# eagle_mini.net
KiCad netlist of a schematic drawn in EAGLE
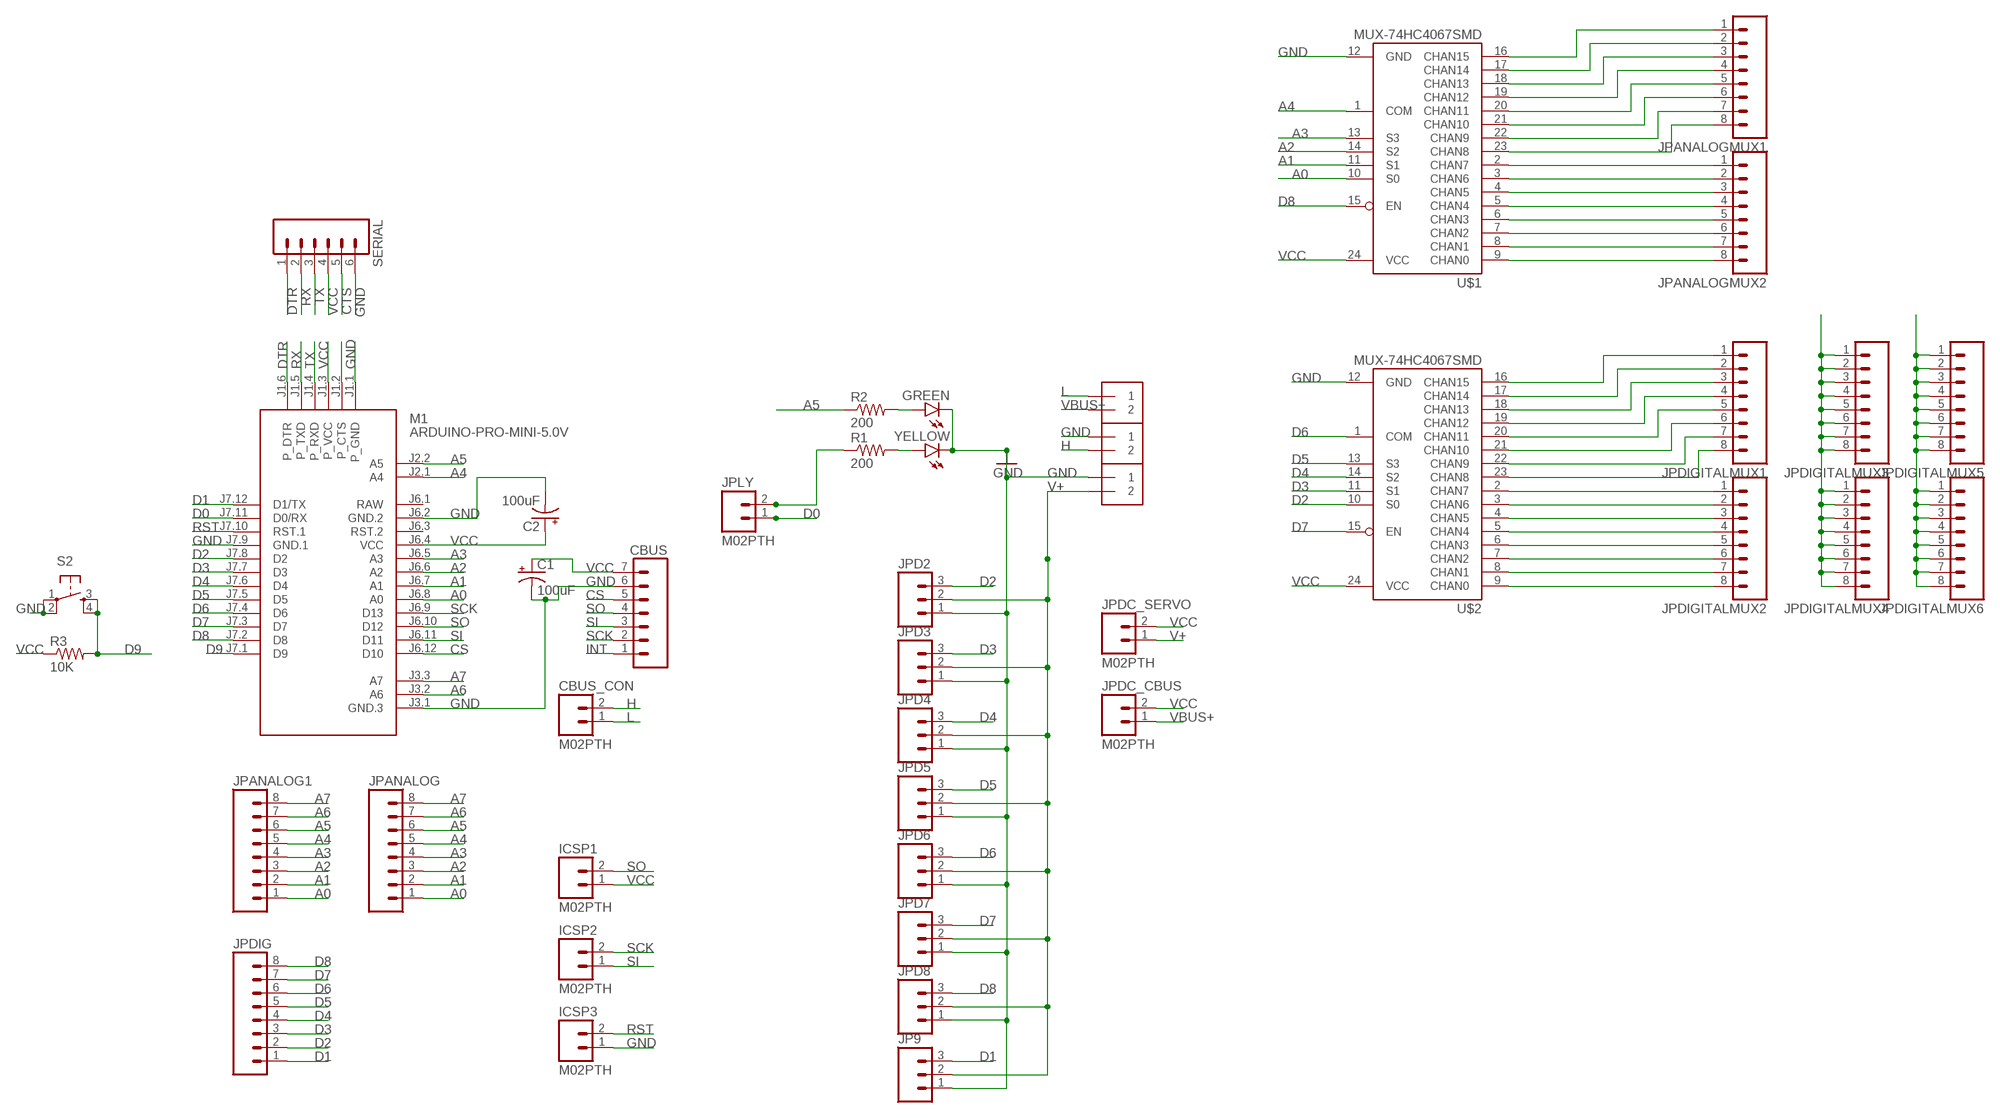
[diagram p0: schematic, sheet 1]

(export (version "E")
  (design (tool "Eeschema 10.0.6"))
  (components
    (comp (ref "C1")
      (value "100uF")
      (footprint "eagle-import:E2,5-6")
      (libsource (lib "eagle-import") (part "CPOL-USE2.5-6"))
    )
    (comp (ref "C2")
      (value "100uF")
      (footprint "eagle-import:E2,5-6")
      (libsource (lib "eagle-import") (part "CPOL-USE2.5-6"))
    )
    (comp (ref "CBUS")
      (value "M07")
      (footprint "eagle-import:1X07")
      (libsource (lib "eagle-import") (part "M07"))
    )
    (comp (ref "CBUS_CON")
      (value "M02PTH")
      (footprint "eagle-import:1X02")
      (libsource (lib "eagle-import") (part "M02PTH"))
    )
    (comp (ref "EXT_VCC")
      (value "1X2-3.5MM")
      (footprint "eagle-import:1X2-3.5MM")
      (libsource (lib "eagle-import") (part "1X2-3.5MM"))
    )
    (comp (ref "GREEN")
      (value "LED-3MM-NO_SILK")
      (footprint "eagle-import:LED3MM-NS")
      (libsource (lib "eagle-import") (part "LED-3MM-NO_SILK"))
    )
    (comp (ref "ICSP1")
      (value "M02PTH")
      (footprint "eagle-import:1X02")
      (libsource (lib "eagle-import") (part "M02PTH"))
    )
    (comp (ref "ICSP2")
      (value "M02PTH")
      (footprint "eagle-import:1X02")
      (libsource (lib "eagle-import") (part "M02PTH"))
    )
    (comp (ref "ICSP3")
      (value "M02PTH")
      (footprint "eagle-import:1X02")
      (libsource (lib "eagle-import") (part "M02PTH"))
    )
    (comp (ref "J1")
      (value "1X2-3.5MM")
      (footprint "eagle-import:1X2-3.5MM")
      (libsource (lib "eagle-import") (part "1X2-3.5MM"))
    )
    (comp (ref "J2")
      (value "1X2-3.5MM")
      (footprint "eagle-import:1X2-3.5MM")
      (libsource (lib "eagle-import") (part "1X2-3.5MM"))
    )
    (comp (ref "JP9")
      (value "M03PTH")
      (footprint "eagle-import:1X03")
      (libsource (lib "eagle-import") (part "M03PTH"))
    )
    (comp (ref "JPANALOG")
      (value "M08")
      (footprint "eagle-import:1X08_ROUND")
      (libsource (lib "eagle-import") (part "M08"))
    )
    (comp (ref "JPANALOG1")
      (value "M08")
      (footprint "eagle-import:1X08_ROUND")
      (libsource (lib "eagle-import") (part "M08"))
    )
    (comp (ref "JPANALOGMUX1")
      (value "M08")
      (footprint "eagle-import:1X08_ROUND")
      (libsource (lib "eagle-import") (part "M08"))
    )
    (comp (ref "JPANALOGMUX2")
      (value "M08")
      (footprint "eagle-import:1X08_ROUND")
      (libsource (lib "eagle-import") (part "M08"))
    )
    (comp (ref "JPD2")
      (value "M03PTH")
      (footprint "eagle-import:1X03")
      (libsource (lib "eagle-import") (part "M03PTH"))
    )
    (comp (ref "JPD3")
      (value "M03PTH")
      (footprint "eagle-import:1X03")
      (libsource (lib "eagle-import") (part "M03PTH"))
    )
    (comp (ref "JPD4")
      (value "M03PTH")
      (footprint "eagle-import:1X03")
      (libsource (lib "eagle-import") (part "M03PTH"))
    )
    (comp (ref "JPD5")
      (value "M03PTH")
      (footprint "eagle-import:1X03")
      (libsource (lib "eagle-import") (part "M03PTH"))
    )
    (comp (ref "JPD6")
      (value "M03PTH")
      (footprint "eagle-import:1X03")
      (libsource (lib "eagle-import") (part "M03PTH"))
    )
    (comp (ref "JPD7")
      (value "M03PTH")
      (footprint "eagle-import:1X03")
      (libsource (lib "eagle-import") (part "M03PTH"))
    )
    (comp (ref "JPD8")
      (value "M03PTH")
      (footprint "eagle-import:1X03")
      (libsource (lib "eagle-import") (part "M03PTH"))
    )
    (comp (ref "JPDC_CBUS")
      (value "M02PTH")
      (footprint "eagle-import:1X02")
      (libsource (lib "eagle-import") (part "M02PTH"))
    )
    (comp (ref "JPDC_SERVO")
      (value "M02PTH")
      (footprint "eagle-import:1X02")
      (libsource (lib "eagle-import") (part "M02PTH"))
    )
    (comp (ref "JPDIG")
      (value "M08")
      (footprint "eagle-import:1X08_ROUND")
      (libsource (lib "eagle-import") (part "M08"))
    )
    (comp (ref "JPDIGITALMUX1")
      (value "M08")
      (footprint "eagle-import:1X08_ROUND")
      (libsource (lib "eagle-import") (part "M08"))
    )
    (comp (ref "JPDIGITALMUX2")
      (value "M08")
      (footprint "eagle-import:1X08_ROUND")
      (libsource (lib "eagle-import") (part "M08"))
    )
    (comp (ref "JPDIGITALMUX3")
      (value "M08")
      (footprint "eagle-import:1X08_ROUND")
      (libsource (lib "eagle-import") (part "M08"))
    )
    (comp (ref "JPDIGITALMUX4")
      (value "M08")
      (footprint "eagle-import:1X08_ROUND")
      (libsource (lib "eagle-import") (part "M08"))
    )
    (comp (ref "JPDIGITALMUX5")
      (value "M08")
      (footprint "eagle-import:1X08_ROUND")
      (libsource (lib "eagle-import") (part "M08"))
    )
    (comp (ref "JPDIGITALMUX6")
      (value "M08")
      (footprint "eagle-import:1X08_ROUND")
      (libsource (lib "eagle-import") (part "M08"))
    )
    (comp (ref "JPLY")
      (value "M02PTH")
      (footprint "eagle-import:1X02")
      (libsource (lib "eagle-import") (part "M02PTH"))
    )
    (comp (ref "M1")
      (value "ARDUINO-PRO-MINI-5.0V")
      (footprint "eagle-import:ARDUINO-PRO-MINI")
      (libsource (lib "eagle-import") (part "ARDUINO-PRO-MINI-5.0V"))
    )
    (comp (ref "R1")
      (value "200")
      (footprint "eagle-import:AXIAL-0.3")
      (libsource (lib "eagle-import") (part "RESISTORAXIAL-0.3"))
    )
    (comp (ref "R2")
      (value "200")
      (footprint "eagle-import:AXIAL-0.3")
      (libsource (lib "eagle-import") (part "RESISTORAXIAL-0.3"))
    )
    (comp (ref "R3")
      (value "10K")
      (footprint "eagle-import:AXIAL-0.3")
      (libsource (lib "eagle-import") (part "RESISTORAXIAL-0.3"))
    )
    (comp (ref "S2")
      (value "TAC_SWITCHPTH")
      (footprint "eagle-import:TACTILE-PTH")
      (libsource (lib "eagle-import") (part "TAC_SWITCHPTH"))
    )
    (comp (ref "SERIAL")
      (value "M06SILK_FEMALE_PTH")
      (footprint "eagle-import:1X06")
      (libsource (lib "eagle-import") (part "M06SILK_FEMALE_PTH"))
    )
    (comp (ref "U$1")
      (value "MUX-74HC4067SMD")
      (footprint "eagle-import:SSOP24")
      (libsource (lib "eagle-import") (part "MUX-74HC4067SMD"))
    )
    (comp (ref "U$2")
      (value "MUX-74HC4067SMD")
      (footprint "eagle-import:SSOP24")
      (libsource (lib "eagle-import") (part "MUX-74HC4067SMD"))
    )
    (comp (ref "YELLOW")
      (value "LED-3MM-NO_SILK")
      (footprint "eagle-import:LED3MM-NS")
      (libsource (lib "eagle-import") (part "LED-3MM-NO_SILK"))
    )
  )
  (nets
    (net (code "1") (name "/A0") (class "Default")
      (node (ref "JPANALOG") (pin "1") (pinfunction "1_1") (pintype "passive"))
      (node (ref "JPANALOG1") (pin "1") (pinfunction "1_1") (pintype "passive"))
      (node (ref "M1") (pin "J6.8") (pinfunction "A0_J6.8") (pintype "bidirectional"))
      (node (ref "U$1") (pin "10") (pinfunction "S0_10") (pintype "input"))
    )
    (net (code "2") (name "/A1") (class "Default")
      (node (ref "JPANALOG") (pin "2") (pinfunction "2_2") (pintype "passive"))
      (node (ref "JPANALOG1") (pin "2") (pinfunction "2_2") (pintype "passive"))
      (node (ref "M1") (pin "J6.7") (pinfunction "A1_J6.7") (pintype "bidirectional"))
      (node (ref "U$1") (pin "11") (pinfunction "S1_11") (pintype "input"))
    )
    (net (code "3") (name "/A2") (class "Default")
      (node (ref "JPANALOG") (pin "3") (pinfunction "3_3") (pintype "passive"))
      (node (ref "JPANALOG1") (pin "3") (pinfunction "3_3") (pintype "passive"))
      (node (ref "M1") (pin "J6.6") (pinfunction "A2_J6.6") (pintype "bidirectional"))
      (node (ref "U$1") (pin "14") (pinfunction "S2_14") (pintype "input"))
    )
    (net (code "4") (name "/A3") (class "Default")
      (node (ref "JPANALOG") (pin "4") (pinfunction "4_4") (pintype "passive"))
      (node (ref "JPANALOG1") (pin "4") (pinfunction "4_4") (pintype "passive"))
      (node (ref "M1") (pin "J6.5") (pinfunction "A3_J6.5") (pintype "bidirectional"))
      (node (ref "U$1") (pin "13") (pinfunction "S3_13") (pintype "input"))
    )
    (net (code "5") (name "/A4") (class "Default")
      (node (ref "JPANALOG") (pin "5") (pinfunction "5_5") (pintype "passive"))
      (node (ref "JPANALOG1") (pin "5") (pinfunction "5_5") (pintype "passive"))
      (node (ref "M1") (pin "J2.1") (pinfunction "A4_J2.1") (pintype "bidirectional"))
      (node (ref "U$1") (pin "1") (pinfunction "COM_1") (pintype "bidirectional"))
    )
    (net (code "6") (name "/A5") (class "Default")
      (node (ref "JPANALOG") (pin "6") (pinfunction "6_6") (pintype "passive"))
      (node (ref "JPANALOG1") (pin "6") (pinfunction "6_6") (pintype "passive"))
      (node (ref "M1") (pin "J2.2") (pinfunction "A5_J2.2") (pintype "bidirectional"))
      (node (ref "R2") (pin "P$1") (pinfunction "1_P$1") (pintype "passive"))
    )
    (net (code "7") (name "/A6") (class "Default")
      (node (ref "JPANALOG") (pin "7") (pinfunction "7_7") (pintype "passive"))
      (node (ref "JPANALOG1") (pin "7") (pinfunction "7_7") (pintype "passive"))
      (node (ref "M1") (pin "J3.2") (pinfunction "A6_J3.2") (pintype "bidirectional"))
    )
    (net (code "8") (name "/A7") (class "Default")
      (node (ref "JPANALOG") (pin "8") (pinfunction "8_8") (pintype "passive"))
      (node (ref "JPANALOG1") (pin "8") (pinfunction "8_8") (pintype "passive"))
      (node (ref "M1") (pin "J3.3") (pinfunction "A7_J3.3") (pintype "bidirectional"))
    )
    (net (code "9") (name "/CS") (class "Default")
      (node (ref "CBUS") (pin "5") (pinfunction "5_5") (pintype "passive"))
      (node (ref "M1") (pin "J6.12") (pinfunction "D10_J6.12") (pintype "bidirectional"))
    )
    (net (code "10") (name "/CTS") (class "Default")
      (node (ref "SERIAL") (pin "5") (pinfunction "5_5") (pintype "passive"))
    )
    (net (code "11") (name "/D0") (class "Default")
      (node (ref "JPLY") (pin "1") (pinfunction "1_1") (pintype "passive"))
      (node (ref "M1") (pin "J7.11") (pinfunction "D0/RX_J7.11") (pintype "bidirectional"))
    )
    (net (code "12") (name "/D1") (class "Default")
      (node (ref "JP9") (pin "3") (pinfunction "3_3") (pintype "passive"))
      (node (ref "JPDIG") (pin "1") (pinfunction "1_1") (pintype "passive"))
      (node (ref "M1") (pin "J7.12") (pinfunction "D1/TX_J7.12") (pintype "bidirectional"))
    )
    (net (code "13") (name "/D2") (class "Default")
      (node (ref "JPD2") (pin "3") (pinfunction "3_3") (pintype "passive"))
      (node (ref "JPDIG") (pin "2") (pinfunction "2_2") (pintype "passive"))
      (node (ref "M1") (pin "J7.8") (pinfunction "D2_J7.8") (pintype "bidirectional"))
      (node (ref "U$2") (pin "10") (pinfunction "S0_10") (pintype "input"))
    )
    (net (code "14") (name "/D3") (class "Default")
      (node (ref "JPD3") (pin "3") (pinfunction "3_3") (pintype "passive"))
      (node (ref "JPDIG") (pin "3") (pinfunction "3_3") (pintype "passive"))
      (node (ref "M1") (pin "J7.7") (pinfunction "D3_J7.7") (pintype "bidirectional"))
      (node (ref "U$2") (pin "11") (pinfunction "S1_11") (pintype "input"))
    )
    (net (code "15") (name "/D4") (class "Default")
      (node (ref "JPD4") (pin "3") (pinfunction "3_3") (pintype "passive"))
      (node (ref "JPDIG") (pin "4") (pinfunction "4_4") (pintype "passive"))
      (node (ref "M1") (pin "J7.6") (pinfunction "D4_J7.6") (pintype "bidirectional"))
      (node (ref "U$2") (pin "14") (pinfunction "S2_14") (pintype "input"))
    )
    (net (code "16") (name "/D5") (class "Default")
      (node (ref "JPD5") (pin "3") (pinfunction "3_3") (pintype "passive"))
      (node (ref "JPDIG") (pin "5") (pinfunction "5_5") (pintype "passive"))
      (node (ref "M1") (pin "J7.5") (pinfunction "D5_J7.5") (pintype "bidirectional"))
      (node (ref "U$2") (pin "13") (pinfunction "S3_13") (pintype "input"))
    )
    (net (code "17") (name "/D6") (class "Default")
      (node (ref "JPD6") (pin "3") (pinfunction "3_3") (pintype "passive"))
      (node (ref "JPDIG") (pin "6") (pinfunction "6_6") (pintype "passive"))
      (node (ref "M1") (pin "J7.4") (pinfunction "D6_J7.4") (pintype "bidirectional"))
      (node (ref "U$2") (pin "1") (pinfunction "COM_1") (pintype "bidirectional"))
    )
    (net (code "18") (name "/D7") (class "Default")
      (node (ref "JPD7") (pin "3") (pinfunction "3_3") (pintype "passive"))
      (node (ref "JPDIG") (pin "7") (pinfunction "7_7") (pintype "passive"))
      (node (ref "M1") (pin "J7.3") (pinfunction "D7_J7.3") (pintype "bidirectional"))
      (node (ref "U$2") (pin "15") (pinfunction "EN_15") (pintype "input"))
    )
    (net (code "19") (name "/D8") (class "Default")
      (node (ref "JPD8") (pin "3") (pinfunction "3_3") (pintype "passive"))
      (node (ref "JPDIG") (pin "8") (pinfunction "8_8") (pintype "passive"))
      (node (ref "M1") (pin "J7.2") (pinfunction "D8_J7.2") (pintype "bidirectional"))
      (node (ref "U$1") (pin "15") (pinfunction "EN_15") (pintype "input"))
    )
    (net (code "20") (name "/D9") (class "Default")
      (node (ref "M1") (pin "J7.1") (pinfunction "D9_J7.1") (pintype "bidirectional"))
      (node (ref "R3") (pin "P$2") (pinfunction "2_P$2") (pintype "passive"))
      (node (ref "S2") (pin "3") (pinfunction "3_3") (pintype "passive"))
      (node (ref "S2") (pin "4") (pinfunction "4_4") (pintype "passive"))
    )
    (net (code "21") (name "/DTR") (class "Default")
      (node (ref "M1") (pin "J1.6") (pinfunction "P_DTR_J1.6") (pintype "bidirectional"))
      (node (ref "SERIAL") (pin "1") (pinfunction "1_1") (pintype "passive"))
    )
    (net (code "22") (name "/H") (class "Default")
      (node (ref "CBUS_CON") (pin "2") (pinfunction "2_2") (pintype "passive"))
      (node (ref "J1") (pin "2") (pinfunction "2_2") (pintype "passive"))
    )
    (net (code "23") (name "/INT") (class "Default")
      (node (ref "CBUS") (pin "1") (pinfunction "1_1") (pintype "passive"))
    )
    (net (code "24") (name "/L") (class "Default")
      (node (ref "CBUS_CON") (pin "1") (pinfunction "1_1") (pintype "passive"))
      (node (ref "J2") (pin "1") (pinfunction "1_1") (pintype "passive"))
    )
    (net (code "25") (name "/RAW") (class "Default")
      (node (ref "M1") (pin "J6.1") (pinfunction "RAW_J6.1") (pintype "power_in"))
    )
    (net (code "26") (name "/RST") (class "Default")
      (node (ref "ICSP3") (pin "2") (pinfunction "2_2") (pintype "passive"))
      (node (ref "M1") (pin "J7.10") (pinfunction "RST.1_J7.10") (pintype "bidirectional"))
    )
    (net (code "27") (name "/RX") (class "Default")
      (node (ref "M1") (pin "J1.5") (pinfunction "P_TXD_J1.5") (pintype "bidirectional"))
      (node (ref "SERIAL") (pin "2") (pinfunction "2_2") (pintype "passive"))
    )
    (net (code "28") (name "/SCK") (class "Default")
      (node (ref "CBUS") (pin "2") (pinfunction "2_2") (pintype "passive"))
      (node (ref "ICSP2") (pin "2") (pinfunction "2_2") (pintype "passive"))
      (node (ref "M1") (pin "J6.9") (pinfunction "D13_J6.9") (pintype "bidirectional"))
    )
    (net (code "29") (name "/SI") (class "Default")
      (node (ref "CBUS") (pin "3") (pinfunction "3_3") (pintype "passive"))
      (node (ref "ICSP2") (pin "1") (pinfunction "1_1") (pintype "passive"))
      (node (ref "M1") (pin "J6.11") (pinfunction "D11_J6.11") (pintype "bidirectional"))
    )
    (net (code "30") (name "/SO") (class "Default")
      (node (ref "CBUS") (pin "4") (pinfunction "4_4") (pintype "passive"))
      (node (ref "ICSP1") (pin "2") (pinfunction "2_2") (pintype "passive"))
      (node (ref "M1") (pin "J6.10") (pinfunction "D12_J6.10") (pintype "bidirectional"))
    )
    (net (code "31") (name "/TX") (class "Default")
      (node (ref "M1") (pin "J1.4") (pinfunction "P_RXD_J1.4") (pintype "bidirectional"))
      (node (ref "SERIAL") (pin "3") (pinfunction "3_3") (pintype "passive"))
    )
    (net (code "32") (name "/V+") (class "Default")
      (node (ref "EXT_VCC") (pin "2") (pinfunction "2_2") (pintype "passive"))
      (node (ref "JP9") (pin "2") (pinfunction "2_2") (pintype "passive"))
      (node (ref "JPD2") (pin "2") (pinfunction "2_2") (pintype "passive"))
      (node (ref "JPD3") (pin "2") (pinfunction "2_2") (pintype "passive"))
      (node (ref "JPD4") (pin "2") (pinfunction "2_2") (pintype "passive"))
      (node (ref "JPD5") (pin "2") (pinfunction "2_2") (pintype "passive"))
      (node (ref "JPD6") (pin "2") (pinfunction "2_2") (pintype "passive"))
      (node (ref "JPD7") (pin "2") (pinfunction "2_2") (pintype "passive"))
      (node (ref "JPD8") (pin "2") (pinfunction "2_2") (pintype "passive"))
      (node (ref "JPDC_SERVO") (pin "1") (pinfunction "1_1") (pintype "passive"))
      (node (ref "JPDIGITALMUX5") (pin "1") (pinfunction "1_1") (pintype "passive"))
      (node (ref "JPDIGITALMUX5") (pin "2") (pinfunction "2_2") (pintype "passive"))
      (node (ref "JPDIGITALMUX5") (pin "3") (pinfunction "3_3") (pintype "passive"))
      (node (ref "JPDIGITALMUX5") (pin "4") (pinfunction "4_4") (pintype "passive"))
      (node (ref "JPDIGITALMUX5") (pin "5") (pinfunction "5_5") (pintype "passive"))
      (node (ref "JPDIGITALMUX5") (pin "6") (pinfunction "6_6") (pintype "passive"))
      (node (ref "JPDIGITALMUX5") (pin "7") (pinfunction "7_7") (pintype "passive"))
      (node (ref "JPDIGITALMUX5") (pin "8") (pinfunction "8_8") (pintype "passive"))
      (node (ref "JPDIGITALMUX6") (pin "1") (pinfunction "1_1") (pintype "passive"))
      (node (ref "JPDIGITALMUX6") (pin "2") (pinfunction "2_2") (pintype "passive"))
      (node (ref "JPDIGITALMUX6") (pin "3") (pinfunction "3_3") (pintype "passive"))
      (node (ref "JPDIGITALMUX6") (pin "4") (pinfunction "4_4") (pintype "passive"))
      (node (ref "JPDIGITALMUX6") (pin "5") (pinfunction "5_5") (pintype "passive"))
      (node (ref "JPDIGITALMUX6") (pin "6") (pinfunction "6_6") (pintype "passive"))
      (node (ref "JPDIGITALMUX6") (pin "7") (pinfunction "7_7") (pintype "passive"))
      (node (ref "JPDIGITALMUX6") (pin "8") (pinfunction "8_8") (pintype "passive"))
    )
    (net (code "33") (name "/VBUS+") (class "Default")
      (node (ref "J2") (pin "2") (pinfunction "2_2") (pintype "passive"))
      (node (ref "JPDC_CBUS") (pin "1") (pinfunction "1_1") (pintype "passive"))
    )
    (net (code "34") (name "/VCC") (class "Default")
      (node (ref "C1") (pin "+") (pinfunction "+_+") (pintype "passive"))
      (node (ref "C2") (pin "+") (pinfunction "+_+") (pintype "passive"))
      (node (ref "CBUS") (pin "7") (pinfunction "7_7") (pintype "passive"))
      (node (ref "ICSP1") (pin "1") (pinfunction "1_1") (pintype "passive"))
      (node (ref "JPDC_CBUS") (pin "2") (pinfunction "2_2") (pintype "passive"))
      (node (ref "JPDC_SERVO") (pin "2") (pinfunction "2_2") (pintype "passive"))
      (node (ref "M1") (pin "J1.3") (pinfunction "P_VCC_J1.3") (pintype "bidirectional"))
      (node (ref "M1") (pin "J6.4") (pinfunction "VCC_J6.4") (pintype "power_in"))
      (node (ref "R3") (pin "P$1") (pinfunction "1_P$1") (pintype "passive"))
      (node (ref "SERIAL") (pin "4") (pinfunction "4_4") (pintype "passive"))
      (node (ref "U$1") (pin "24") (pinfunction "VCC_24") (pintype "bidirectional"))
      (node (ref "U$2") (pin "24") (pinfunction "VCC_24") (pintype "bidirectional"))
    )
    (net (code "35") (name "GND") (class "Default")
      (node (ref "C1") (pin "-") (pinfunction "-_-") (pintype "passive"))
      (node (ref "C2") (pin "-") (pinfunction "-_-") (pintype "passive"))
      (node (ref "CBUS") (pin "6") (pinfunction "6_6") (pintype "passive"))
      (node (ref "EXT_VCC") (pin "1") (pinfunction "1_1") (pintype "passive"))
      (node (ref "GREEN") (pin "K") (pinfunction "C_K") (pintype "passive"))
      (node (ref "ICSP3") (pin "1") (pinfunction "1_1") (pintype "passive"))
      (node (ref "J1") (pin "1") (pinfunction "1_1") (pintype "passive"))
      (node (ref "JP9") (pin "1") (pinfunction "1_1") (pintype "passive"))
      (node (ref "JPD2") (pin "1") (pinfunction "1_1") (pintype "passive"))
      (node (ref "JPD3") (pin "1") (pinfunction "1_1") (pintype "passive"))
      (node (ref "JPD4") (pin "1") (pinfunction "1_1") (pintype "passive"))
      (node (ref "JPD5") (pin "1") (pinfunction "1_1") (pintype "passive"))
      (node (ref "JPD6") (pin "1") (pinfunction "1_1") (pintype "passive"))
      (node (ref "JPD7") (pin "1") (pinfunction "1_1") (pintype "passive"))
      (node (ref "JPD8") (pin "1") (pinfunction "1_1") (pintype "passive"))
      (node (ref "JPDIGITALMUX3") (pin "1") (pinfunction "1_1") (pintype "passive"))
      (node (ref "JPDIGITALMUX3") (pin "2") (pinfunction "2_2") (pintype "passive"))
      (node (ref "JPDIGITALMUX3") (pin "3") (pinfunction "3_3") (pintype "passive"))
      (node (ref "JPDIGITALMUX3") (pin "4") (pinfunction "4_4") (pintype "passive"))
      (node (ref "JPDIGITALMUX3") (pin "5") (pinfunction "5_5") (pintype "passive"))
      (node (ref "JPDIGITALMUX3") (pin "6") (pinfunction "6_6") (pintype "passive"))
      (node (ref "JPDIGITALMUX3") (pin "7") (pinfunction "7_7") (pintype "passive"))
      (node (ref "JPDIGITALMUX3") (pin "8") (pinfunction "8_8") (pintype "passive"))
      (node (ref "JPDIGITALMUX4") (pin "1") (pinfunction "1_1") (pintype "passive"))
      (node (ref "JPDIGITALMUX4") (pin "2") (pinfunction "2_2") (pintype "passive"))
      (node (ref "JPDIGITALMUX4") (pin "3") (pinfunction "3_3") (pintype "passive"))
      (node (ref "JPDIGITALMUX4") (pin "4") (pinfunction "4_4") (pintype "passive"))
      (node (ref "JPDIGITALMUX4") (pin "5") (pinfunction "5_5") (pintype "passive"))
      (node (ref "JPDIGITALMUX4") (pin "6") (pinfunction "6_6") (pintype "passive"))
      (node (ref "JPDIGITALMUX4") (pin "7") (pinfunction "7_7") (pintype "passive"))
      (node (ref "JPDIGITALMUX4") (pin "8") (pinfunction "8_8") (pintype "passive"))
      (node (ref "M1") (pin "J1.1") (pinfunction "P_GND_J1.1") (pintype "bidirectional"))
      (node (ref "M1") (pin "J3.1") (pinfunction "GND.3_J3.1") (pintype "bidirectional"))
      (node (ref "M1") (pin "J6.2") (pinfunction "GND.2_J6.2") (pintype "power_in"))
      (node (ref "M1") (pin "J7.9") (pinfunction "GND.1_J7.9") (pintype "power_in"))
      (node (ref "S2") (pin "1") (pinfunction "1_1") (pintype "passive"))
      (node (ref "S2") (pin "2") (pinfunction "2_2") (pintype "passive"))
      (node (ref "SERIAL") (pin "6") (pinfunction "6_6") (pintype "passive"))
      (node (ref "U$1") (pin "12") (pinfunction "GND_12") (pintype "bidirectional"))
      (node (ref "U$2") (pin "12") (pinfunction "GND_12") (pintype "bidirectional"))
      (node (ref "YELLOW") (pin "K") (pinfunction "C_K") (pintype "passive"))
    )
    (net (code "36") (name "Net-(R1-1)") (class "Default")
      (node (ref "JPLY") (pin "2") (pinfunction "2_2") (pintype "passive"))
      (node (ref "R1") (pin "P$1") (pinfunction "1_P$1") (pintype "passive"))
    )
    (net (code "37") (name "Net-(R1-2)") (class "Default")
      (node (ref "R1") (pin "P$2") (pinfunction "2_P$2") (pintype "passive"))
      (node (ref "YELLOW") (pin "A") (pinfunction "A_A") (pintype "passive"))
    )
    (net (code "38") (name "Net-(R2-2)") (class "Default")
      (node (ref "GREEN") (pin "A") (pinfunction "A_A") (pintype "passive"))
      (node (ref "R2") (pin "P$2") (pinfunction "2_P$2") (pintype "passive"))
    )
    (net (code "39") (name "Net-(U$1-CHAN0)") (class "Default")
      (node (ref "JPANALOGMUX2") (pin "8") (pinfunction "8_8") (pintype "passive"))
      (node (ref "U$1") (pin "9") (pinfunction "CHAN0_9") (pintype "bidirectional"))
    )
    (net (code "40") (name "Net-(U$1-CHAN1)") (class "Default")
      (node (ref "JPANALOGMUX2") (pin "7") (pinfunction "7_7") (pintype "passive"))
      (node (ref "U$1") (pin "8") (pinfunction "CHAN1_8") (pintype "bidirectional"))
    )
    (net (code "41") (name "Net-(U$1-CHAN2)") (class "Default")
      (node (ref "JPANALOGMUX2") (pin "6") (pinfunction "6_6") (pintype "passive"))
      (node (ref "U$1") (pin "7") (pinfunction "CHAN2_7") (pintype "bidirectional"))
    )
    (net (code "42") (name "Net-(U$1-CHAN3)") (class "Default")
      (node (ref "JPANALOGMUX2") (pin "5") (pinfunction "5_5") (pintype "passive"))
      (node (ref "U$1") (pin "6") (pinfunction "CHAN3_6") (pintype "bidirectional"))
    )
    (net (code "43") (name "Net-(U$1-CHAN4)") (class "Default")
      (node (ref "JPANALOGMUX2") (pin "4") (pinfunction "4_4") (pintype "passive"))
      (node (ref "U$1") (pin "5") (pinfunction "CHAN4_5") (pintype "bidirectional"))
    )
    (net (code "44") (name "Net-(U$1-CHAN5)") (class "Default")
      (node (ref "JPANALOGMUX2") (pin "3") (pinfunction "3_3") (pintype "passive"))
      (node (ref "U$1") (pin "4") (pinfunction "CHAN5_4") (pintype "bidirectional"))
    )
    (net (code "45") (name "Net-(U$1-CHAN6)") (class "Default")
      (node (ref "JPANALOGMUX2") (pin "2") (pinfunction "2_2") (pintype "passive"))
      (node (ref "U$1") (pin "3") (pinfunction "CHAN6_3") (pintype "bidirectional"))
    )
    (net (code "46") (name "Net-(U$1-CHAN7)") (class "Default")
      (node (ref "JPANALOGMUX2") (pin "1") (pinfunction "1_1") (pintype "passive"))
      (node (ref "U$1") (pin "2") (pinfunction "CHAN7_2") (pintype "bidirectional"))
    )
    (net (code "47") (name "Net-(U$1-CHAN8)") (class "Default")
      (node (ref "JPANALOGMUX1") (pin "8") (pinfunction "8_8") (pintype "passive"))
      (node (ref "U$1") (pin "23") (pinfunction "CHAN8_23") (pintype "bidirectional"))
    )
    (net (code "48") (name "Net-(U$1-CHAN9)") (class "Default")
      (node (ref "JPANALOGMUX1") (pin "7") (pinfunction "7_7") (pintype "passive"))
      (node (ref "U$1") (pin "22") (pinfunction "CHAN9_22") (pintype "bidirectional"))
    )
    (net (code "49") (name "Net-(U$1-CHAN10)") (class "Default")
      (node (ref "JPANALOGMUX1") (pin "6") (pinfunction "6_6") (pintype "passive"))
      (node (ref "U$1") (pin "21") (pinfunction "CHAN10_21") (pintype "bidirectional"))
    )
    (net (code "50") (name "Net-(U$1-CHAN11)") (class "Default")
      (node (ref "JPANALOGMUX1") (pin "5") (pinfunction "5_5") (pintype "passive"))
      (node (ref "U$1") (pin "20") (pinfunction "CHAN11_20") (pintype "bidirectional"))
    )
    (net (code "51") (name "Net-(U$1-CHAN12)") (class "Default")
      (node (ref "JPANALOGMUX1") (pin "4") (pinfunction "4_4") (pintype "passive"))
      (node (ref "U$1") (pin "19") (pinfunction "CHAN12_19") (pintype "bidirectional"))
    )
    (net (code "52") (name "Net-(U$1-CHAN13)") (class "Default")
      (node (ref "JPANALOGMUX1") (pin "3") (pinfunction "3_3") (pintype "passive"))
      (node (ref "U$1") (pin "18") (pinfunction "CHAN13_18") (pintype "bidirectional"))
    )
    (net (code "53") (name "Net-(U$1-CHAN14)") (class "Default")
      (node (ref "JPANALOGMUX1") (pin "2") (pinfunction "2_2") (pintype "passive"))
      (node (ref "U$1") (pin "17") (pinfunction "CHAN14_17") (pintype "bidirectional"))
    )
    (net (code "54") (name "Net-(U$1-CHAN15)") (class "Default")
      (node (ref "JPANALOGMUX1") (pin "1") (pinfunction "1_1") (pintype "passive"))
      (node (ref "U$1") (pin "16") (pinfunction "CHAN15_16") (pintype "bidirectional"))
    )
    (net (code "55") (name "Net-(U$2-CHAN0)") (class "Default")
      (node (ref "JPDIGITALMUX2") (pin "8") (pinfunction "8_8") (pintype "passive"))
      (node (ref "U$2") (pin "9") (pinfunction "CHAN0_9") (pintype "bidirectional"))
    )
    (net (code "56") (name "Net-(U$2-CHAN1)") (class "Default")
      (node (ref "JPDIGITALMUX2") (pin "7") (pinfunction "7_7") (pintype "passive"))
      (node (ref "U$2") (pin "8") (pinfunction "CHAN1_8") (pintype "bidirectional"))
    )
    (net (code "57") (name "Net-(U$2-CHAN2)") (class "Default")
      (node (ref "JPDIGITALMUX2") (pin "6") (pinfunction "6_6") (pintype "passive"))
      (node (ref "U$2") (pin "7") (pinfunction "CHAN2_7") (pintype "bidirectional"))
    )
    (net (code "58") (name "Net-(U$2-CHAN3)") (class "Default")
      (node (ref "JPDIGITALMUX2") (pin "5") (pinfunction "5_5") (pintype "passive"))
      (node (ref "U$2") (pin "6") (pinfunction "CHAN3_6") (pintype "bidirectional"))
    )
    (net (code "59") (name "Net-(U$2-CHAN4)") (class "Default")
      (node (ref "JPDIGITALMUX2") (pin "4") (pinfunction "4_4") (pintype "passive"))
      (node (ref "U$2") (pin "5") (pinfunction "CHAN4_5") (pintype "bidirectional"))
    )
    (net (code "60") (name "Net-(U$2-CHAN5)") (class "Default")
      (node (ref "JPDIGITALMUX2") (pin "3") (pinfunction "3_3") (pintype "passive"))
      (node (ref "U$2") (pin "4") (pinfunction "CHAN5_4") (pintype "bidirectional"))
    )
    (net (code "61") (name "Net-(U$2-CHAN6)") (class "Default")
      (node (ref "JPDIGITALMUX2") (pin "2") (pinfunction "2_2") (pintype "passive"))
      (node (ref "U$2") (pin "3") (pinfunction "CHAN6_3") (pintype "bidirectional"))
    )
    (net (code "62") (name "Net-(U$2-CHAN7)") (class "Default")
      (node (ref "JPDIGITALMUX2") (pin "1") (pinfunction "1_1") (pintype "passive"))
      (node (ref "U$2") (pin "2") (pinfunction "CHAN7_2") (pintype "bidirectional"))
    )
    (net (code "63") (name "Net-(U$2-CHAN8)") (class "Default")
      (node (ref "JPDIGITALMUX1") (pin "8") (pinfunction "8_8") (pintype "passive"))
      (node (ref "U$2") (pin "23") (pinfunction "CHAN8_23") (pintype "bidirectional"))
    )
    (net (code "64") (name "Net-(U$2-CHAN9)") (class "Default")
      (node (ref "JPDIGITALMUX1") (pin "7") (pinfunction "7_7") (pintype "passive"))
      (node (ref "U$2") (pin "22") (pinfunction "CHAN9_22") (pintype "bidirectional"))
    )
    (net (code "65") (name "Net-(U$2-CHAN10)") (class "Default")
      (node (ref "JPDIGITALMUX1") (pin "6") (pinfunction "6_6") (pintype "passive"))
      (node (ref "U$2") (pin "21") (pinfunction "CHAN10_21") (pintype "bidirectional"))
    )
    (net (code "66") (name "Net-(U$2-CHAN11)") (class "Default")
      (node (ref "JPDIGITALMUX1") (pin "5") (pinfunction "5_5") (pintype "passive"))
      (node (ref "U$2") (pin "20") (pinfunction "CHAN11_20") (pintype "bidirectional"))
    )
    (net (code "67") (name "Net-(U$2-CHAN12)") (class "Default")
      (node (ref "JPDIGITALMUX1") (pin "4") (pinfunction "4_4") (pintype "passive"))
      (node (ref "U$2") (pin "19") (pinfunction "CHAN12_19") (pintype "bidirectional"))
    )
    (net (code "68") (name "Net-(U$2-CHAN13)") (class "Default")
      (node (ref "JPDIGITALMUX1") (pin "3") (pinfunction "3_3") (pintype "passive"))
      (node (ref "U$2") (pin "18") (pinfunction "CHAN13_18") (pintype "bidirectional"))
    )
    (net (code "69") (name "Net-(U$2-CHAN14)") (class "Default")
      (node (ref "JPDIGITALMUX1") (pin "2") (pinfunction "2_2") (pintype "passive"))
      (node (ref "U$2") (pin "17") (pinfunction "CHAN14_17") (pintype "bidirectional"))
    )
    (net (code "70") (name "Net-(U$2-CHAN15)") (class "Default")
      (node (ref "JPDIGITALMUX1") (pin "1") (pinfunction "1_1") (pintype "passive"))
      (node (ref "U$2") (pin "16") (pinfunction "CHAN15_16") (pintype "bidirectional"))
    )
    (net (code "71") (name "unconnected-(M1-P_CTS-PadJ1.2)") (class "Default")
      (node (ref "M1") (pin "J1.2") (pinfunction "P_CTS_J1.2") (pintype "bidirectional"))
    )
    (net (code "72") (name "unconnected-(M1-RST.2-PadJ6.3)") (class "Default")
      (node (ref "M1") (pin "J6.3") (pinfunction "RST.2_J6.3") (pintype "bidirectional"))
    )
  )
)
